# Rectifier.net
KiCad netlist of a schematic drawn in Altium Designer
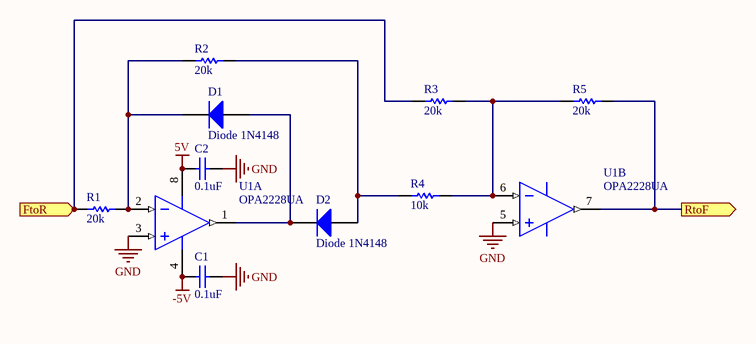
[diagram p0: Rectifier.SchDoc]

(export (version "E")
  (design (tool "Eeschema 10.0.6"))
  (components
    (comp (ref "C1")
      (value "0.1uF")
      (footprint "RAD-0.3")
      (description "Capacitor")
      (fields (field (name "Comment") "Cap") (field (name "PUBLISHER") "Altium Limited"))
      (libsource (lib "Miscellaneous Devices") (part "Cap"))
    )
    (comp (ref "C2")
      (value "0.1uF")
      (footprint "RAD-0.3")
      (description "Capacitor")
      (fields (field (name "Comment") "Cap") (field (name "PUBLISHER") "Altium Limited"))
      (libsource (lib "Miscellaneous Devices") (part "Cap"))
    )
    (comp (ref "D1")
      (value "Diode 1N4148")
      (footprint "DO-35")
      (description "High Conductance Fast Diode")
      (fields (field (name "PUBLISHER") "Altium Limited"))
      (libsource (lib "Miscellaneous Devices") (part "Diode 1N4148"))
    )
    (comp (ref "D2")
      (value "Diode 1N4148")
      (footprint "DO-35")
      (description "High Conductance Fast Diode")
      (fields (field (name "PUBLISHER") "Altium Limited"))
      (libsource (lib "Miscellaneous Devices") (part "Diode 1N4148"))
    )
    (comp (ref "R1")
      (value "20k")
      (footprint "AXIAL-0.3")
      (description "Resistor")
      (fields (field (name "Comment") "Res1") (field (name "PUBLISHER") "Altium Limited"))
      (libsource (lib "Miscellaneous Devices") (part "Res1"))
    )
    (comp (ref "R2")
      (value "20k")
      (footprint "AXIAL-0.3")
      (description "Resistor")
      (fields (field (name "Comment") "Res1") (field (name "PUBLISHER") "Altium Limited"))
      (libsource (lib "Miscellaneous Devices") (part "Res1"))
    )
    (comp (ref "R3")
      (value "20k")
      (footprint "AXIAL-0.3")
      (description "Resistor")
      (fields (field (name "Comment") "Res1") (field (name "PUBLISHER") "Altium Limited"))
      (libsource (lib "Miscellaneous Devices") (part "Res1"))
    )
    (comp (ref "R4")
      (value "10k")
      (footprint "AXIAL-0.3")
      (description "Resistor")
      (fields (field (name "Comment") "Res1") (field (name "PUBLISHER") "Altium Limited"))
      (libsource (lib "Miscellaneous Devices") (part "Res1"))
    )
    (comp (ref "R5")
      (value "20k")
      (footprint "AXIAL-0.3")
      (description "Resistor")
      (fields (field (name "Comment") "Res1") (field (name "PUBLISHER") "Altium Limited"))
      (libsource (lib "Miscellaneous Devices") (part "Res1"))
    )
    (comp (ref "U1")
      (value "OPA2228UA")
      (footprint "TI-D8_N")
      (fields (field (name "MANUFACTURER") "Texas Instruments"))
      (libsource (lib "TI Amplifiers and Linear Operational Amplifier Precision Amplifier Part One") (part "OPA2228UA"))
    )
  )
  (nets
    (net (code "1") (name "-5V") (class "Default")
      (node (ref "C1") (pin "2") (pinfunction "2_2") (pintype "passive"))
      (node (ref "U1") (pin "4") (pinfunction "V-_4") (pintype "power_in"))
    )
    (net (code "2") (name "/FtoR") (class "Default")
      (node (ref "R1") (pin "2") (pinfunction "2_2") (pintype "passive"))
      (node (ref "R3") (pin "2") (pinfunction "2_2") (pintype "passive"))
    )
    (net (code "3") (name "/RtoF") (class "Default")
      (node (ref "R5") (pin "1") (pinfunction "1_1") (pintype "passive"))
      (node (ref "U1") (pin "7") (pinfunction "OUT_B_7") (pintype "output"))
    )
    (net (code "4") (name "5V") (class "Default")
      (node (ref "C2") (pin "2") (pinfunction "2_2") (pintype "passive"))
      (node (ref "U1") (pin "8") (pinfunction "V+_8") (pintype "power_in"))
    )
    (net (code "5") (name "GND") (class "Default")
      (node (ref "C1") (pin "1") (pinfunction "1_1") (pintype "passive"))
      (node (ref "C2") (pin "1") (pinfunction "1_1") (pintype "passive"))
      (node (ref "U1") (pin "3") (pinfunction "IN_A+_3") (pintype "input"))
      (node (ref "U1") (pin "5") (pinfunction "IN_B+_5") (pintype "input"))
    )
    (net (code "6") (name "Net-(D1-A)") (class "Default")
      (node (ref "D1") (pin "1") (pinfunction "A_1") (pintype "passive"))
      (node (ref "D2") (pin "2") (pinfunction "K_2") (pintype "passive"))
      (node (ref "U1") (pin "1") (pinfunction "OUT_A_1") (pintype "output"))
    )
    (net (code "7") (name "Net-(D1-K)") (class "Default")
      (node (ref "D1") (pin "2") (pinfunction "K_2") (pintype "passive"))
      (node (ref "R1") (pin "1") (pinfunction "1_1") (pintype "passive"))
      (node (ref "R2") (pin "2") (pinfunction "2_2") (pintype "passive"))
      (node (ref "U1") (pin "2") (pinfunction "IN_A-_2") (pintype "input"))
    )
    (net (code "8") (name "Net-(D2-A)") (class "Default")
      (node (ref "D2") (pin "1") (pinfunction "A_1") (pintype "passive"))
      (node (ref "R2") (pin "1") (pinfunction "1_1") (pintype "passive"))
      (node (ref "R4") (pin "2") (pinfunction "2_2") (pintype "passive"))
    )
    (net (code "9") (name "Net-(U1B-IN_B-)") (class "Default")
      (node (ref "R3") (pin "1") (pinfunction "1_1") (pintype "passive"))
      (node (ref "R4") (pin "1") (pinfunction "1_1") (pintype "passive"))
      (node (ref "R5") (pin "2") (pinfunction "2_2") (pintype "passive"))
      (node (ref "U1") (pin "6") (pinfunction "IN_B-_6") (pintype "input"))
    )
  )
)
